# uLI-04.net
KiCad netlist of a schematic drawn in EAGLE
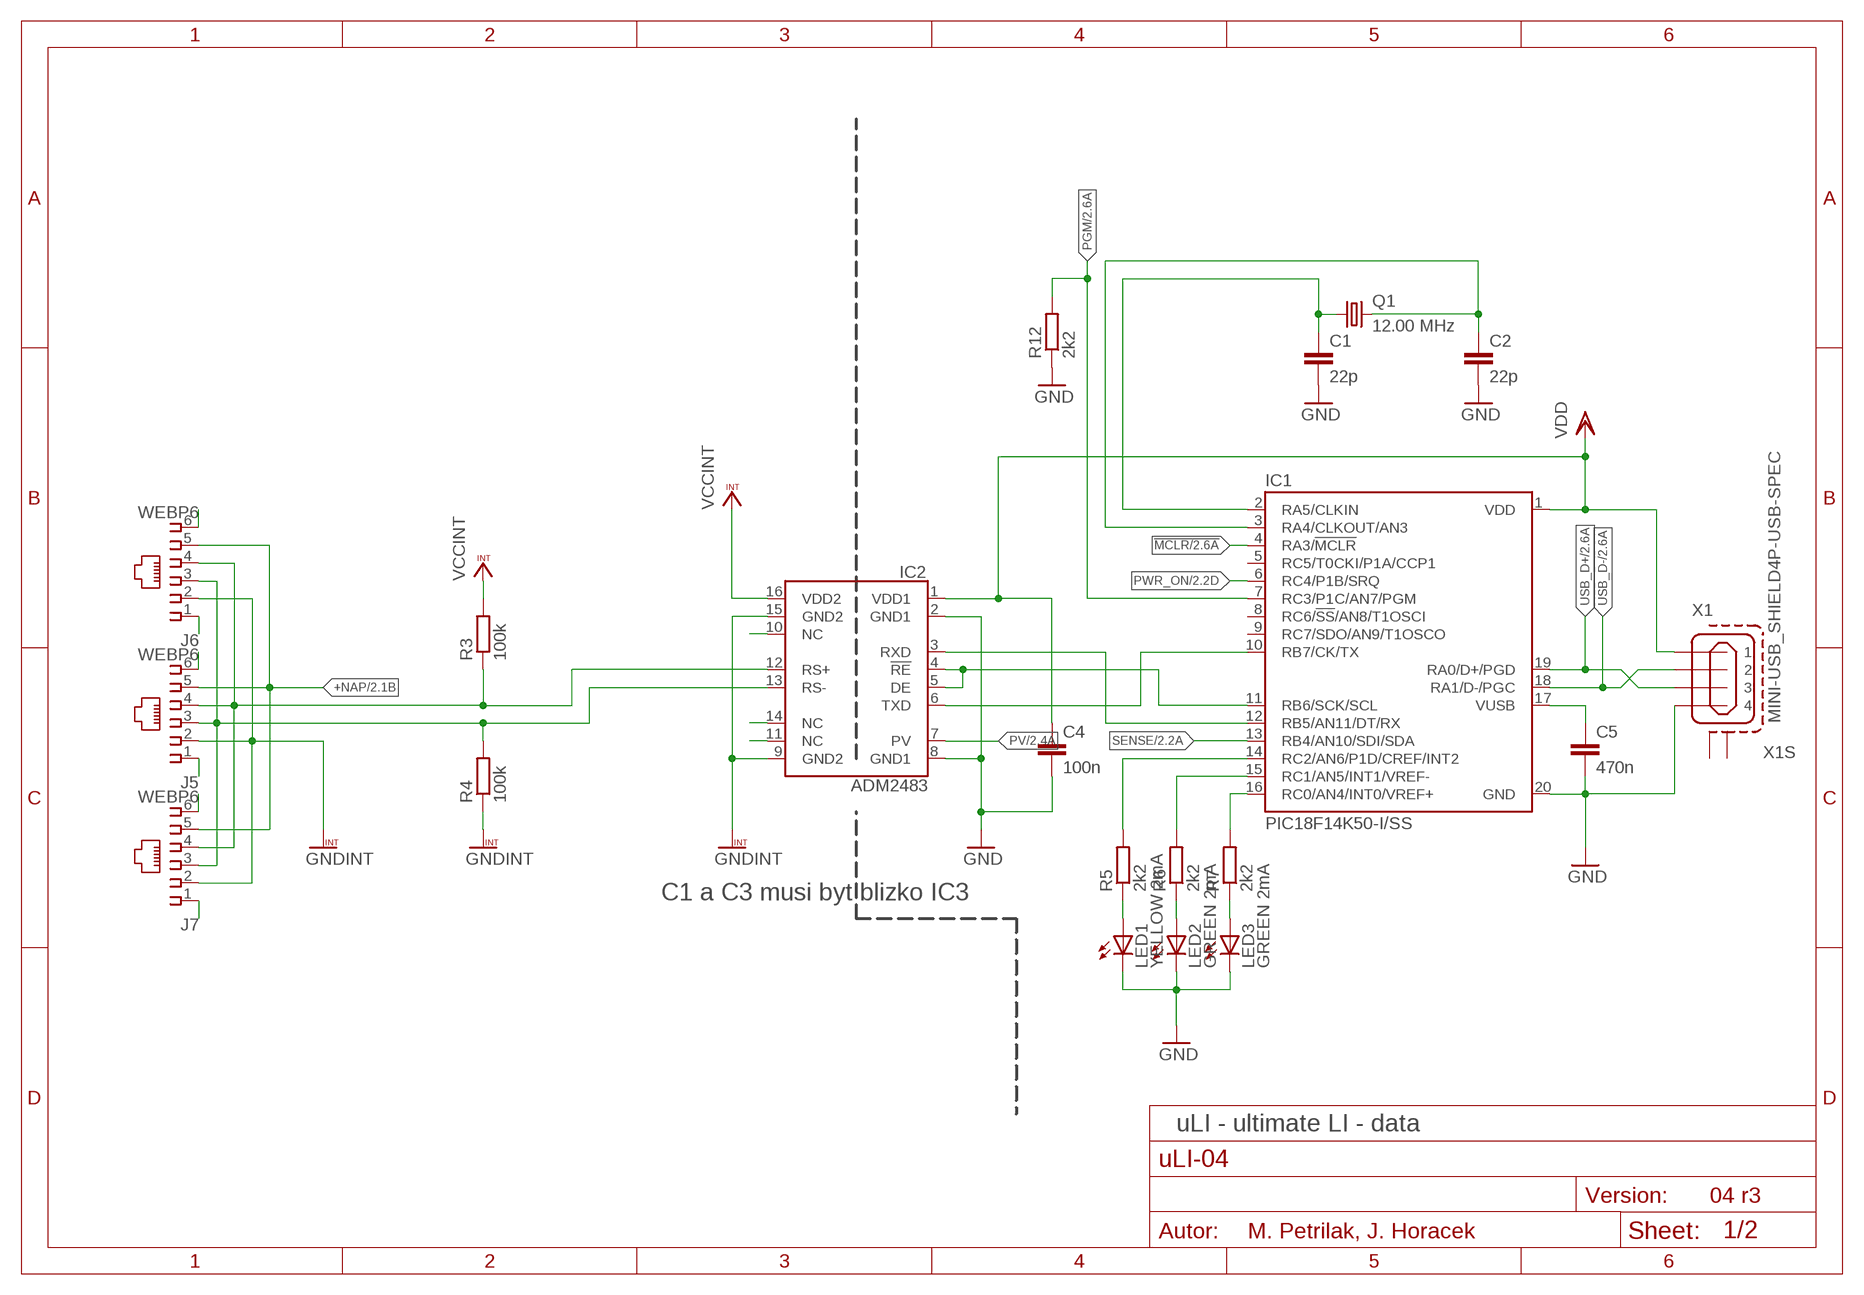
[diagram p0: schematic, sheet 1]
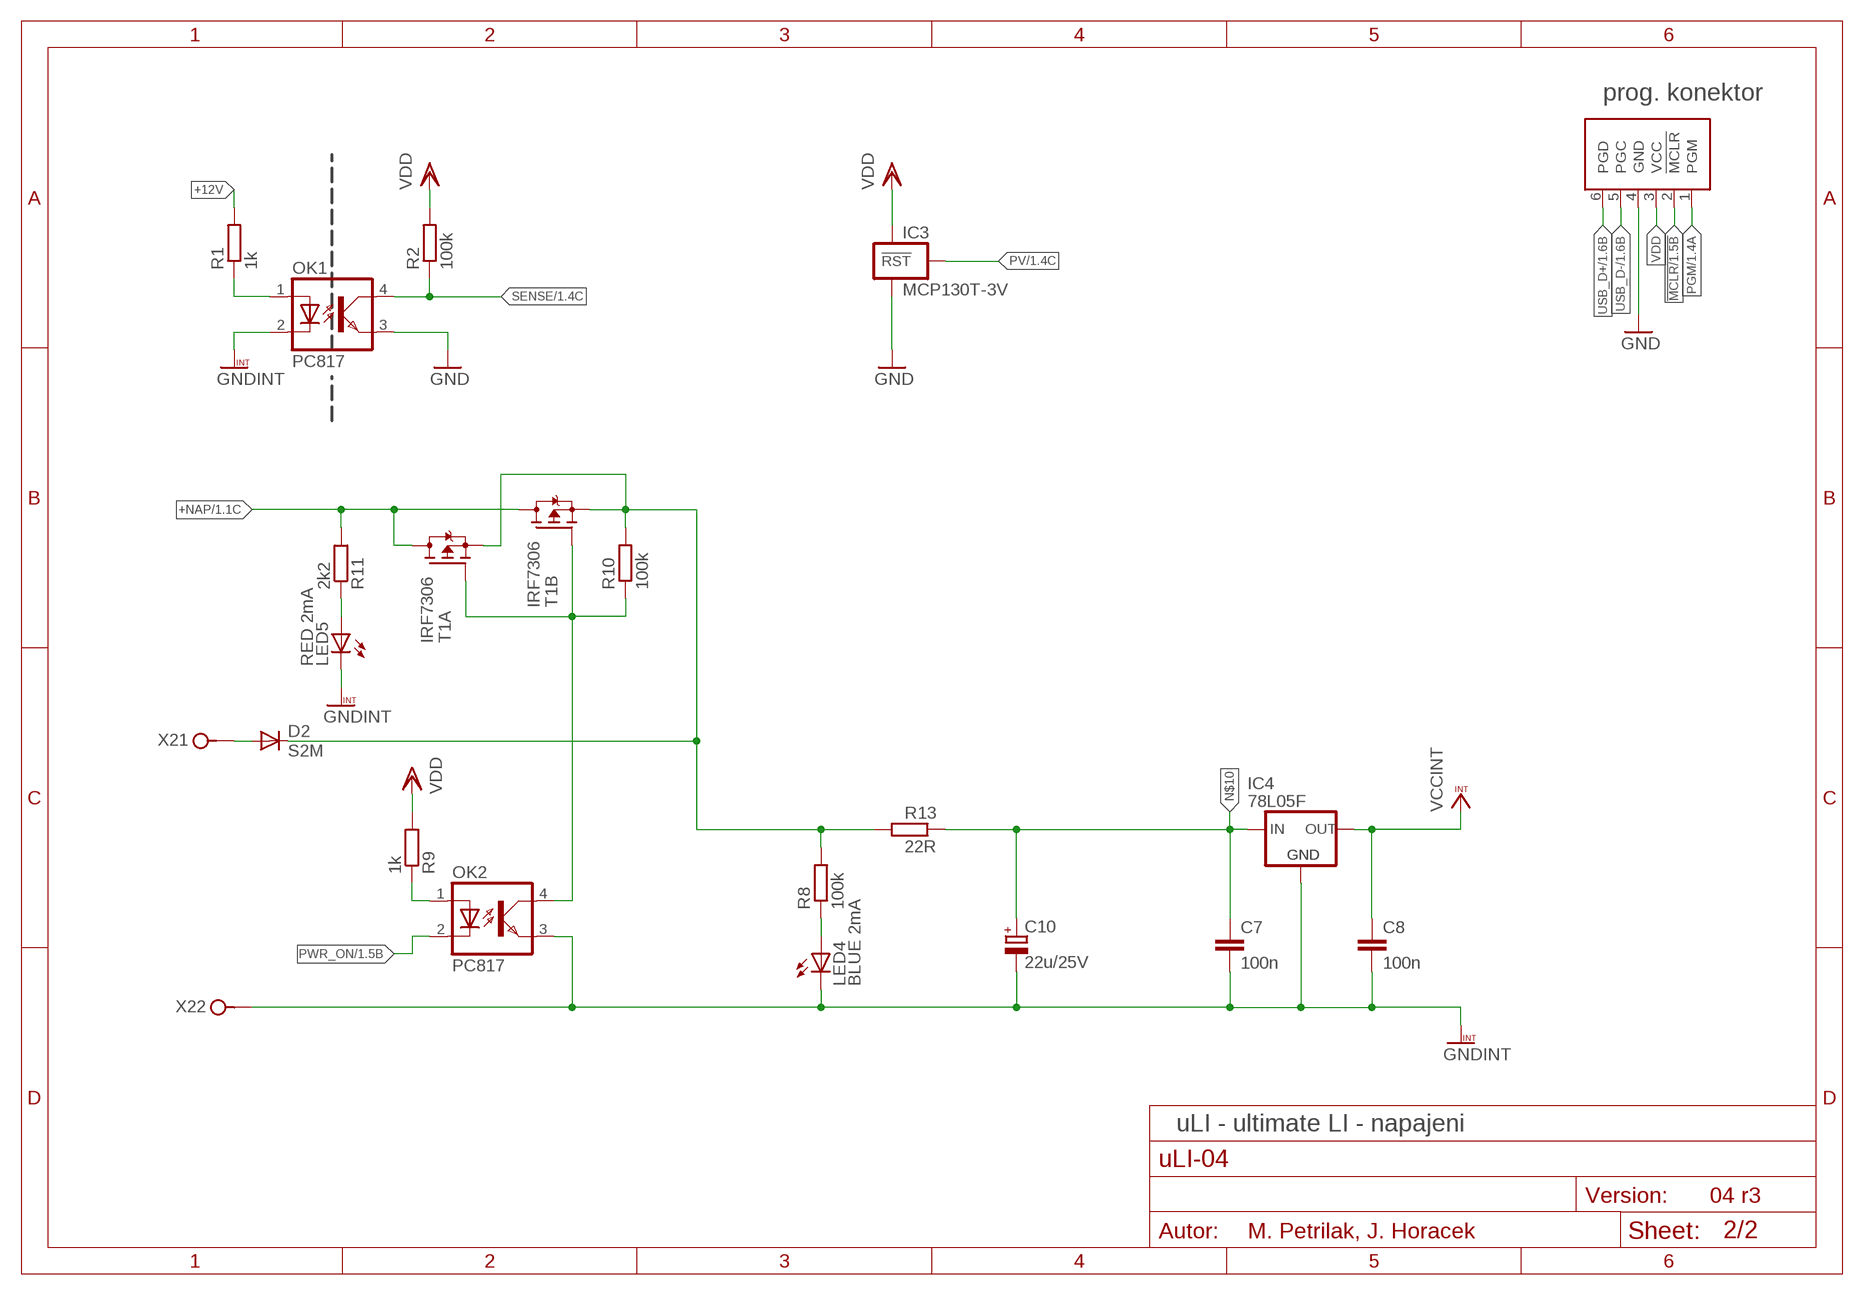
[diagram p1: schematic, sheet 2]

(export (version "E")
  (design (tool "Eeschema 10.0.6"))
  (components
    (comp (ref "C1")
      (value "22p")
      (footprint "eagle-import:C0805")
      (libsource (lib "eagle-import") (part "C-EUC0805"))
    )
    (comp (ref "C2")
      (value "22p")
      (footprint "eagle-import:C0805")
      (libsource (lib "eagle-import") (part "C-EUC0805"))
    )
    (comp (ref "C4")
      (value "100n")
      (footprint "eagle-import:C1206")
      (libsource (lib "eagle-import") (part "C-EUC1206"))
    )
    (comp (ref "C5")
      (value "470n")
      (footprint "eagle-import:C1206")
      (libsource (lib "eagle-import") (part "C-EUC1206"))
    )
    (comp (ref "IC1")
      (value "PIC18F14K50-I/SS")
      (footprint "eagle-import:SSOP20")
      (libsource (lib "eagle-import") (part "PIC18K50-I/SSF14"))
    )
    (comp (ref "IC2")
      (value "ADM2483")
      (footprint "eagle-import:SO-16W")
      (libsource (lib "eagle-import") (part "ADM2483"))
    )
    (comp (ref "J5")
      (value "WEBP6")
      (footprint "eagle-import:WEBP6-6_SPEC2")
      (libsource (lib "eagle-import") (part "WEBP6-6_SPEC2"))
    )
    (comp (ref "J6")
      (value "WEBP6")
      (footprint "eagle-import:WEBP6-6_SPEC2")
      (libsource (lib "eagle-import") (part "WEBP6-6_SPEC2"))
    )
    (comp (ref "J7")
      (value "WEBP6")
      (footprint "eagle-import:WEBP6-6_SPEC2")
      (libsource (lib "eagle-import") (part "WEBP6-6_SPEC2"))
    )
    (comp (ref "LED1")
      (value "YELLOW 2mA")
      (footprint "eagle-import:LED3MM")
      (libsource (lib "eagle-import") (part "LED3MM"))
    )
    (comp (ref "LED2")
      (value "GREEN 2mA")
      (footprint "eagle-import:LED3MM")
      (libsource (lib "eagle-import") (part "LED3MM"))
    )
    (comp (ref "LED3")
      (value "GREEN 2mA")
      (footprint "eagle-import:LED3MM")
      (libsource (lib "eagle-import") (part "LED3MM"))
    )
    (comp (ref "Q1")
      (value "12.00 MHz")
      (footprint "eagle-import:HC49U70")
      (libsource (lib "eagle-import") (part "XTAL"))
    )
    (comp (ref "R3")
      (value "100k")
      (footprint "eagle-import:R1206")
      (libsource (lib "eagle-import") (part "R-EU_R1206"))
    )
    (comp (ref "R4")
      (value "100k")
      (footprint "eagle-import:R1206")
      (libsource (lib "eagle-import") (part "R-EU_R1206"))
    )
    (comp (ref "R5")
      (value "2k2")
      (footprint "eagle-import:R1206")
      (libsource (lib "eagle-import") (part "R-EU_R1206"))
    )
    (comp (ref "R6")
      (value "2k2")
      (footprint "eagle-import:R1206")
      (libsource (lib "eagle-import") (part "R-EU_R1206"))
    )
    (comp (ref "R7")
      (value "2k2")
      (footprint "eagle-import:R1206")
      (libsource (lib "eagle-import") (part "R-EU_R1206"))
    )
    (comp (ref "R12")
      (value "2k2")
      (footprint "eagle-import:R1206")
      (libsource (lib "eagle-import") (part "R-EU_R1206"))
    )
    (comp (ref "X1")
      (value "MINI-USB_SHIELD4P-USB-SPEC")
      (footprint "eagle-import:85-32004-10X-SPEC")
      (libsource (lib "eagle-import") (part "MINI-USB_SHIELD4P-USB-SPEC"))
    )
    (comp (ref "C7")
      (value "100n")
      (footprint "eagle-import:C1206")
      (libsource (lib "eagle-import") (part "C-EUC1206"))
    )
    (comp (ref "C8")
      (value "100n")
      (footprint "eagle-import:C1206")
      (libsource (lib "eagle-import") (part "C-EUC1206"))
    )
    (comp (ref "C10")
      (value "22u/25V")
      (footprint "eagle-import:E2-5")
      (libsource (lib "eagle-import") (part "CPOL-EUE2-5"))
    )
    (comp (ref "D2")
      (value "S2M")
      (footprint "eagle-import:SMB")
      (libsource (lib "eagle-import") (part "S2M"))
    )
    (comp (ref "IC3")
      (value "MCP130T-3V")
      (footprint "eagle-import:SOT23")
      (libsource (lib "eagle-import") (part "MCP130T"))
    )
    (comp (ref "IC4")
      (value "78L05F")
      (footprint "eagle-import:SOT89")
      (libsource (lib "eagle-import") (part "78LF05"))
    )
    (comp (ref "J1")
      (value "PICPROG2-V")
      (footprint "eagle-import:6410-06-PICPROG")
      (libsource (lib "eagle-import") (part "PICPROG2-V"))
    )
    (comp (ref "LED4")
      (value "BLUE 2mA")
      (footprint "eagle-import:LED3MM")
      (libsource (lib "eagle-import") (part "LED3MM"))
    )
    (comp (ref "LED5")
      (value "RED 2mA")
      (footprint "eagle-import:LED3MM")
      (libsource (lib "eagle-import") (part "LED3MM"))
    )
    (comp (ref "OK1")
      (value "PC817")
      (footprint "eagle-import:DIL04")
      (libsource (lib "eagle-import") (part "PC817"))
    )
    (comp (ref "OK2")
      (value "PC817")
      (footprint "eagle-import:DIL04")
      (libsource (lib "eagle-import") (part "PC817"))
    )
    (comp (ref "R1")
      (value "1k")
      (footprint "eagle-import:R1206")
      (libsource (lib "eagle-import") (part "R-EU_R1206"))
    )
    (comp (ref "R2")
      (value "100k")
      (footprint "eagle-import:R1206")
      (libsource (lib "eagle-import") (part "R-EU_R1206"))
    )
    (comp (ref "R8")
      (value "100k")
      (footprint "eagle-import:R1206")
      (libsource (lib "eagle-import") (part "R-EU_R1206"))
    )
    (comp (ref "R9")
      (value "1k")
      (footprint "eagle-import:R1206")
      (libsource (lib "eagle-import") (part "R-EU_R1206"))
    )
    (comp (ref "R10")
      (value "100k")
      (footprint "eagle-import:R1206")
      (libsource (lib "eagle-import") (part "R-EU_R1206"))
    )
    (comp (ref "R11")
      (value "2k2")
      (footprint "eagle-import:R1206")
      (libsource (lib "eagle-import") (part "R-EU_R1206"))
    )
    (comp (ref "R13")
      (value "22R")
      (footprint "eagle-import:R1206")
      (libsource (lib "eagle-import") (part "R-EU_R1206"))
    )
    (comp (ref "T1")
      (value "IRF7306")
      (footprint "eagle-import:SO08-IRF")
      (libsource (lib "eagle-import") (part "IRF7306"))
    )
    (comp (ref "X2")
      (value "ARK1550/2_S")
      (footprint "eagle-import:ARK1550_2_SPEC")
      (libsource (lib "eagle-import") (part "ARK1550/2_S"))
    )
  )
  (nets
    (net (code "1") (name "+12V") (class "Default")
      (node (ref "D2") (pin "C") (pinfunction "C_C") (pintype "passive"))
      (node (ref "R1") (pin "2") (pinfunction "2_2") (pintype "passive"))
      (node (ref "R10") (pin "2") (pinfunction "2_2") (pintype "passive"))
      (node (ref "R13") (pin "2") (pinfunction "2_2") (pintype "passive"))
      (node (ref "R8") (pin "2") (pinfunction "2_2") (pintype "passive"))
      (node (ref "T1") (pin "1") (pinfunction "S_1") (pintype "passive"))
      (node (ref "T1") (pin "3") (pinfunction "S_3") (pintype "passive"))
    )
    (net (code "2") (name "+NAP") (class "Default")
      (node (ref "J5") (pin "5") (pinfunction "5_5") (pintype "passive"))
      (node (ref "J6") (pin "5") (pinfunction "5_5") (pintype "passive"))
      (node (ref "J7") (pin "5") (pinfunction "5_5") (pintype "passive"))
      (node (ref "R11") (pin "2") (pinfunction "2_2") (pintype "passive"))
      (node (ref "T1") (pin "5") (pinfunction "D_5") (pintype "passive"))
      (node (ref "T1") (pin "6") (pinfunction "D_6") (pintype "passive"))
      (node (ref "T1") (pin "7") (pinfunction "D_7") (pintype "passive"))
      (node (ref "T1") (pin "8") (pinfunction "D_8") (pintype "passive"))
    )
    (net (code "3") (name "GND") (class "Default")
      (node (ref "C1") (pin "2") (pinfunction "2_2") (pintype "passive"))
      (node (ref "C2") (pin "2") (pinfunction "2_2") (pintype "passive"))
      (node (ref "C4") (pin "2") (pinfunction "2_2") (pintype "passive"))
      (node (ref "C5") (pin "2") (pinfunction "2_2") (pintype "passive"))
      (node (ref "IC1") (pin "20") (pinfunction "GND_20") (pintype "power_in"))
      (node (ref "IC2") (pin "2") (pinfunction "GND1_2") (pintype "power_in"))
      (node (ref "IC2") (pin "8") (pinfunction "GND1_8") (pintype "power_in"))
      (node (ref "IC3") (pin "3") (pinfunction "GND_3") (pintype "power_in"))
      (node (ref "J1") (pin "4") (pinfunction "GND_4") (pintype "power_in"))
      (node (ref "LED1") (pin "K") (pinfunction "C_K") (pintype "passive"))
      (node (ref "LED2") (pin "K") (pinfunction "C_K") (pintype "passive"))
      (node (ref "LED3") (pin "K") (pinfunction "C_K") (pintype "passive"))
      (node (ref "OK1") (pin "3") (pinfunction "EMIT_3") (pintype "passive"))
      (node (ref "R12") (pin "1") (pinfunction "1_1") (pintype "passive"))
      (node (ref "X1") (pin "4") (pinfunction "4_4") (pintype "passive"))
    )
    (net (code "4") (name "GNDINT") (class "Default")
      (node (ref "C10") (pin "-") (pinfunction "-_-") (pintype "passive"))
      (node (ref "C7") (pin "2") (pinfunction "2_2") (pintype "passive"))
      (node (ref "C8") (pin "2") (pinfunction "2_2") (pintype "passive"))
      (node (ref "IC2") (pin "15") (pinfunction "GND2_15") (pintype "power_in"))
      (node (ref "IC2") (pin "9") (pinfunction "GND2_9") (pintype "power_in"))
      (node (ref "IC4") (pin "2") (pinfunction "GND_2") (pintype "passive"))
      (node (ref "IC4") (pin "2@1") (pinfunction "GND_2@1") (pintype "passive"))
      (node (ref "J5") (pin "2") (pinfunction "2_2") (pintype "passive"))
      (node (ref "J6") (pin "2") (pinfunction "2_2") (pintype "passive"))
      (node (ref "J7") (pin "2") (pinfunction "2_2") (pintype "passive"))
      (node (ref "LED4") (pin "K") (pinfunction "C_K") (pintype "passive"))
      (node (ref "LED5") (pin "K") (pinfunction "C_K") (pintype "passive"))
      (node (ref "OK1") (pin "2") (pinfunction "C_2") (pintype "passive"))
      (node (ref "OK2") (pin "3") (pinfunction "EMIT_3") (pintype "passive"))
      (node (ref "R4") (pin "1") (pinfunction "1_1") (pintype "passive"))
      (node (ref "X2") (pin "2") (pinfunction "1_2") (pintype "passive"))
    )
    (net (code "5") (name "N$10") (class "Default")
      (node (ref "C10") (pin "+") (pinfunction "+_+") (pintype "passive"))
      (node (ref "C7") (pin "1") (pinfunction "1_1") (pintype "passive"))
      (node (ref "IC4") (pin "3") (pinfunction "VI_3") (pintype "input"))
      (node (ref "R13") (pin "1") (pinfunction "1_1") (pintype "passive"))
    )
    (net (code "6") (name "Net-(D2-PadA)") (class "Default")
      (node (ref "D2") (pin "A") (pinfunction "A_A") (pintype "passive"))
      (node (ref "X2") (pin "1") (pinfunction "1_1") (pintype "passive"))
    )
    (net (code "7") (name "Net-(IC1-RA4{slash}CLKOUT{slash}AN3)") (class "Default")
      (node (ref "C2") (pin "1") (pinfunction "1_1") (pintype "passive"))
      (node (ref "IC1") (pin "3") (pinfunction "RA4/CLKOUT/AN3_3") (pintype "bidirectional"))
      (node (ref "Q1") (pin "2") (pinfunction "2_2") (pintype "passive"))
    )
    (net (code "8") (name "Net-(IC1-RA5{slash}CLKIN)") (class "Default")
      (node (ref "C1") (pin "1") (pinfunction "1_1") (pintype "passive"))
      (node (ref "IC1") (pin "2") (pinfunction "RA5/CLKIN_2") (pintype "bidirectional"))
      (node (ref "Q1") (pin "1") (pinfunction "1_1") (pintype "passive"))
    )
    (net (code "9") (name "Net-(IC1-RB5{slash}AN11{slash}DT{slash}RX)") (class "Default")
      (node (ref "IC1") (pin "12") (pinfunction "RB5/AN11/DT/RX_12") (pintype "bidirectional"))
      (node (ref "IC2") (pin "3") (pinfunction "RXD_3") (pintype "input"))
    )
    (net (code "10") (name "Net-(IC1-RB6{slash}SCK{slash}SCL)") (class "Default")
      (node (ref "IC1") (pin "11") (pinfunction "RB6/SCK/SCL_11") (pintype "bidirectional"))
      (node (ref "IC2") (pin "4") (pinfunction "~{RE}_4") (pintype "input"))
      (node (ref "IC2") (pin "5") (pinfunction "DE_5") (pintype "input"))
    )
    (net (code "11") (name "Net-(IC1-RB7{slash}CK{slash}TX)") (class "Default")
      (node (ref "IC1") (pin "10") (pinfunction "RB7/CK/TX_10") (pintype "bidirectional"))
      (node (ref "IC2") (pin "6") (pinfunction "TXD_6") (pintype "output"))
    )
    (net (code "12") (name "Net-(IC1-RC0{slash}AN4{slash}INT0{slash}VREF+)") (class "Default")
      (node (ref "IC1") (pin "16") (pinfunction "RC0/AN4/INT0/VREF+_16") (pintype "bidirectional"))
      (node (ref "R7") (pin "2") (pinfunction "2_2") (pintype "passive"))
    )
    (net (code "13") (name "Net-(IC1-RC1{slash}AN5{slash}INT1{slash}VREF-)") (class "Default")
      (node (ref "IC1") (pin "15") (pinfunction "RC1/AN5/INT1/VREF-_15") (pintype "bidirectional"))
      (node (ref "R6") (pin "2") (pinfunction "2_2") (pintype "passive"))
    )
    (net (code "14") (name "Net-(IC1-RC2{slash}AN6{slash}P1D{slash}CREF{slash}INT2)") (class "Default")
      (node (ref "IC1") (pin "14") (pinfunction "RC2/AN6/P1D/CREF/INT2_14") (pintype "bidirectional"))
      (node (ref "R5") (pin "2") (pinfunction "2_2") (pintype "passive"))
    )
    (net (code "15") (name "Net-(IC1-VUSB)") (class "Default")
      (node (ref "C5") (pin "1") (pinfunction "1_1") (pintype "passive"))
      (node (ref "IC1") (pin "17") (pinfunction "VUSB_17") (pintype "bidirectional"))
    )
    (net (code "16") (name "Net-(IC2-RS+)") (class "Default")
      (node (ref "IC2") (pin "12") (pinfunction "RS+_12") (pintype "output"))
      (node (ref "J5") (pin "4") (pinfunction "4_4") (pintype "passive"))
      (node (ref "J6") (pin "4") (pinfunction "4_4") (pintype "passive"))
      (node (ref "J7") (pin "4") (pinfunction "4_4") (pintype "passive"))
      (node (ref "R3") (pin "1") (pinfunction "1_1") (pintype "passive"))
    )
    (net (code "17") (name "Net-(IC2-RS-)") (class "Default")
      (node (ref "IC2") (pin "13") (pinfunction "RS-_13") (pintype "output"))
      (node (ref "J5") (pin "3") (pinfunction "3_3") (pintype "passive"))
      (node (ref "J6") (pin "3") (pinfunction "3_3") (pintype "passive"))
      (node (ref "J7") (pin "3") (pinfunction "3_3") (pintype "passive"))
      (node (ref "R4") (pin "2") (pinfunction "2_2") (pintype "passive"))
    )
    (net (code "18") (name "Net-(LED1-PadA)") (class "Default")
      (node (ref "LED1") (pin "A") (pinfunction "A_A") (pintype "passive"))
      (node (ref "R5") (pin "1") (pinfunction "1_1") (pintype "passive"))
    )
    (net (code "19") (name "Net-(LED2-PadA)") (class "Default")
      (node (ref "LED2") (pin "A") (pinfunction "A_A") (pintype "passive"))
      (node (ref "R6") (pin "1") (pinfunction "1_1") (pintype "passive"))
    )
    (net (code "20") (name "Net-(LED3-PadA)") (class "Default")
      (node (ref "LED3") (pin "A") (pinfunction "A_A") (pintype "passive"))
      (node (ref "R7") (pin "1") (pinfunction "1_1") (pintype "passive"))
    )
    (net (code "21") (name "Net-(LED4-PadA)") (class "Default")
      (node (ref "LED4") (pin "A") (pinfunction "A_A") (pintype "passive"))
      (node (ref "R8") (pin "1") (pinfunction "1_1") (pintype "passive"))
    )
    (net (code "22") (name "Net-(LED5-PadA)") (class "Default")
      (node (ref "LED5") (pin "A") (pinfunction "A_A") (pintype "passive"))
      (node (ref "R11") (pin "1") (pinfunction "1_1") (pintype "passive"))
    )
    (net (code "23") (name "Net-(OK1-A)") (class "Default")
      (node (ref "OK1") (pin "1") (pinfunction "A_1") (pintype "passive"))
      (node (ref "R1") (pin "1") (pinfunction "1_1") (pintype "passive"))
    )
    (net (code "24") (name "Net-(OK2-A)") (class "Default")
      (node (ref "OK2") (pin "1") (pinfunction "A_1") (pintype "passive"))
      (node (ref "R9") (pin "1") (pinfunction "1_1") (pintype "passive"))
    )
    (net (code "25") (name "Net-(OK2-COL)") (class "Default")
      (node (ref "OK2") (pin "4") (pinfunction "COL_4") (pintype "passive"))
      (node (ref "R10") (pin "1") (pinfunction "1_1") (pintype "passive"))
      (node (ref "T1") (pin "2") (pinfunction "G_2") (pintype "passive"))
      (node (ref "T1") (pin "4") (pinfunction "G_4") (pintype "passive"))
    )
    (net (code "26") (name "PGM") (class "Default")
      (node (ref "IC1") (pin "7") (pinfunction "RC3/P1C/AN7/PGM_7") (pintype "bidirectional"))
      (node (ref "J1") (pin "1") (pinfunction "PGM_1") (pintype "output"))
      (node (ref "R12") (pin "2") (pinfunction "2_2") (pintype "passive"))
    )
    (net (code "27") (name "PV") (class "Default")
      (node (ref "IC2") (pin "7") (pinfunction "PV_7") (pintype "input"))
      (node (ref "IC3") (pin "1") (pinfunction "~{RST}_1") (pintype "output"))
    )
    (net (code "28") (name "PWR_ON") (class "Default")
      (node (ref "IC1") (pin "6") (pinfunction "RC4/P1B/SRQ_6") (pintype "bidirectional"))
      (node (ref "OK2") (pin "2") (pinfunction "C_2") (pintype "passive"))
    )
    (net (code "29") (name "SENSE") (class "Default")
      (node (ref "IC1") (pin "13") (pinfunction "RB4/AN10/SDI/SDA_13") (pintype "bidirectional"))
      (node (ref "OK1") (pin "4") (pinfunction "COL_4") (pintype "passive"))
      (node (ref "R2") (pin "1") (pinfunction "1_1") (pintype "passive"))
    )
    (net (code "30") (name "USB_D+") (class "Default")
      (node (ref "IC1") (pin "19") (pinfunction "RA0/D+/PGD_19") (pintype "bidirectional"))
      (node (ref "J1") (pin "6") (pinfunction "PGD_6") (pintype "input"))
      (node (ref "X1") (pin "3") (pinfunction "3_3") (pintype "passive"))
    )
    (net (code "31") (name "USB_D-") (class "Default")
      (node (ref "IC1") (pin "18") (pinfunction "RA1/D-/PGC_18") (pintype "bidirectional"))
      (node (ref "J1") (pin "5") (pinfunction "PGC_5") (pintype "output"))
      (node (ref "X1") (pin "2") (pinfunction "2_2") (pintype "passive"))
    )
    (net (code "32") (name "VCCINT") (class "Default")
      (node (ref "C8") (pin "1") (pinfunction "1_1") (pintype "passive"))
      (node (ref "IC2") (pin "16") (pinfunction "VDD2_16") (pintype "power_in"))
      (node (ref "IC4") (pin "1") (pinfunction "VO_1") (pintype "passive"))
      (node (ref "R3") (pin "2") (pinfunction "2_2") (pintype "passive"))
    )
    (net (code "33") (name "VDD") (class "Default")
      (node (ref "C4") (pin "1") (pinfunction "1_1") (pintype "passive"))
      (node (ref "IC1") (pin "1") (pinfunction "VDD_1") (pintype "power_in"))
      (node (ref "IC2") (pin "1") (pinfunction "VDD1_1") (pintype "power_in"))
      (node (ref "IC3") (pin "2") (pinfunction "VCC_2") (pintype "power_in"))
      (node (ref "J1") (pin "3") (pinfunction "VCC_3") (pintype "power_in"))
      (node (ref "R2") (pin "2") (pinfunction "2_2") (pintype "passive"))
      (node (ref "R9") (pin "2") (pinfunction "2_2") (pintype "passive"))
      (node (ref "X1") (pin "1") (pinfunction "1_1") (pintype "passive"))
    )
    (net (code "34") (name "unconnected-(IC1-RC5{slash}T0CKI{slash}P1A{slash}CCP1-Pad5)") (class "Default")
      (node (ref "IC1") (pin "5") (pinfunction "RC5/T0CKI/P1A/CCP1_5") (pintype "bidirectional"))
    )
    (net (code "35") (name "unconnected-(IC1-RC6{slash}~{SS}{slash}AN8{slash}T1OSCI-Pad8)") (class "Default")
      (node (ref "IC1") (pin "8") (pinfunction "RC6/~{SS}/AN8/T1OSCI_8") (pintype "bidirectional"))
    )
    (net (code "36") (name "unconnected-(IC1-RC7{slash}SDO{slash}AN9{slash}T1OSCO-Pad9)") (class "Default")
      (node (ref "IC1") (pin "9") (pinfunction "RC7/SDO/AN9/T1OSCO_9") (pintype "bidirectional"))
    )
    (net (code "37") (name "unconnected-(IC2-NC-Pad10)") (class "Default")
      (node (ref "IC2") (pin "10") (pinfunction "NC_10") (pintype "passive"))
    )
    (net (code "38") (name "unconnected-(IC2-NC-Pad11)") (class "Default")
      (node (ref "IC2") (pin "11") (pinfunction "NC_11") (pintype "passive"))
    )
    (net (code "39") (name "unconnected-(IC2-NC-Pad14)") (class "Default")
      (node (ref "IC2") (pin "14") (pinfunction "NC_14") (pintype "passive"))
    )
    (net (code "40") (name "unconnected-(J5-Pad1)") (class "Default")
      (node (ref "J5") (pin "1") (pinfunction "1_1") (pintype "passive"))
    )
    (net (code "41") (name "unconnected-(J5-Pad6)") (class "Default")
      (node (ref "J5") (pin "6") (pinfunction "6_6") (pintype "passive"))
    )
    (net (code "42") (name "unconnected-(J6-Pad1)") (class "Default")
      (node (ref "J6") (pin "1") (pinfunction "1_1") (pintype "passive"))
    )
    (net (code "43") (name "unconnected-(J6-Pad6)") (class "Default")
      (node (ref "J6") (pin "6") (pinfunction "6_6") (pintype "passive"))
    )
    (net (code "44") (name "unconnected-(J7-Pad1)") (class "Default")
      (node (ref "J7") (pin "1") (pinfunction "1_1") (pintype "passive"))
    )
    (net (code "45") (name "unconnected-(J7-Pad6)") (class "Default")
      (node (ref "J7") (pin "6") (pinfunction "6_6") (pintype "passive"))
    )
    (net (code "46") (name "unconnected-(X1B-S1-PadM1)") (class "Default")
      (node (ref "X1") (pin "M1") (pinfunction "S1_M1") (pintype "passive"))
    )
    (net (code "47") (name "unconnected-(X1B-S2-PadM2)") (class "Default")
      (node (ref "X1") (pin "M2") (pinfunction "S2_M2") (pintype "passive"))
    )
    (net (code "48") (name "~{MCLR}") (class "Default")
      (node (ref "IC1") (pin "4") (pinfunction "RA3/~{MCLR}_4") (pintype "bidirectional"))
      (node (ref "J1") (pin "2") (pinfunction "~{MCLR}_2") (pintype "output"))
    )
  )
)
